# LOGIC_MCU.net
KiCad netlist of a schematic drawn in Altium Designer
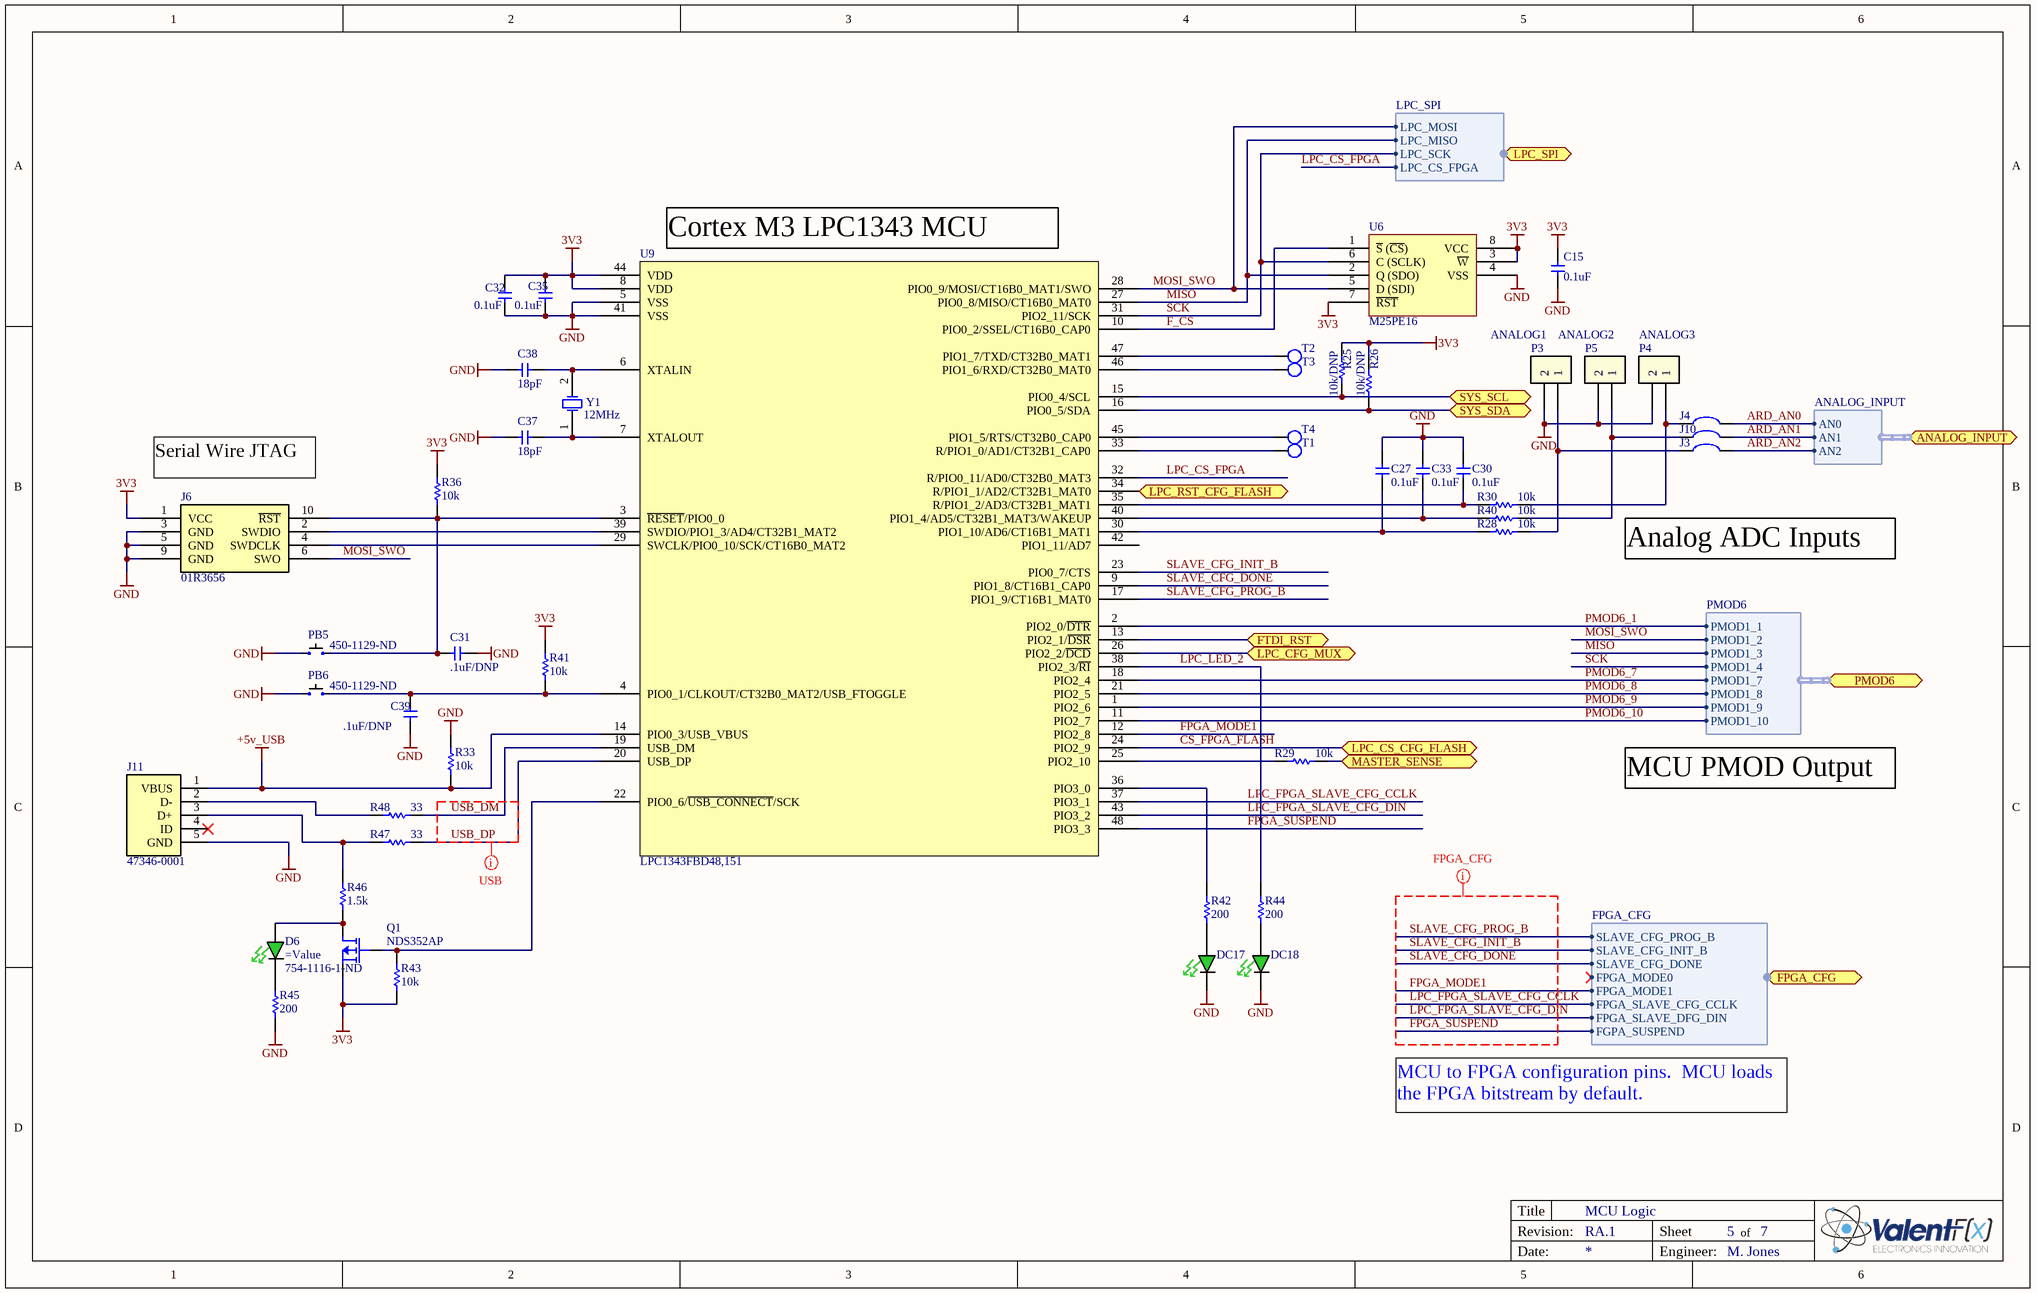
[diagram p0: LOGIC_MCU.SchDoc]

(export (version "E")
  (design (tool "Eeschema 10.0.6"))
  (components
    (comp (ref "C15")
      (value "0.1uF")
      (footprint "C0603")
      (description "CAP CER .1UF 50V 10% X7R 0603")
      (fields
        (field (name "MANUFACTURER") "Murata Electronics North America")
        (field (name "MANUFACTURER PART NUMBER") "GRM188R71H104KA93D")
      )
      (libsource (lib "Capacitors") (part "GRM188R71H104KA93D"))
    )
    (comp (ref "C27")
      (value "0.1uF")
      (footprint "C0603")
      (description "CAP CER .1UF 50V 10% X7R 0603")
      (fields
        (field (name "MANUFACTURER") "Murata Electronics North America")
        (field (name "MANUFACTURER PART NUMBER") "GRM188R71H104KA93D")
      )
      (libsource (lib "Capacitors") (part "GRM188R71H104KA93D"))
    )
    (comp (ref "C30")
      (value "0.1uF")
      (footprint "C0603")
      (description "CAP CER .1UF 50V 10% X7R 0603")
      (fields
        (field (name "MANUFACTURER") "Murata Electronics North America")
        (field (name "MANUFACTURER PART NUMBER") "GRM188R71H104KA93D")
      )
      (libsource (lib "Capacitors") (part "GRM188R71H104KA93D"))
    )
    (comp (ref "C31")
      (value ".1uF/DNP")
      (footprint "C0603")
      (description "CAP CER .1UF 50V 10% X7R 0603")
      (fields
        (field (name "MANUFACTURER") "Murata Electronics North America")
        (field (name "MANUFACTURER PART NUMBER") "GRM188R71H104KA93D")
      )
      (libsource (lib "Capacitors") (part "GRM188R71H104KA93D"))
    )
    (comp (ref "C32")
      (value "0.1uF")
      (footprint "C0603")
      (description "CAP CER .1UF 50V 10% X7R 0603")
      (fields
        (field (name "MANUFACTURER") "Murata Electronics North America")
        (field (name "MANUFACTURER PART NUMBER") "GRM188R71H104KA93D")
      )
      (libsource (lib "Capacitors") (part "GRM188R71H104KA93D"))
    )
    (comp (ref "C33")
      (value "0.1uF")
      (footprint "C0603")
      (description "CAP CER .1UF 50V 10% X7R 0603")
      (fields
        (field (name "MANUFACTURER") "Murata Electronics North America")
        (field (name "MANUFACTURER PART NUMBER") "GRM188R71H104KA93D")
      )
      (libsource (lib "Capacitors") (part "GRM188R71H104KA93D"))
    )
    (comp (ref "C35")
      (value "0.1uF")
      (footprint "C0603")
      (description "CAP CER .1UF 50V 10% X7R 0603")
      (fields
        (field (name "MANUFACTURER") "Murata Electronics North America")
        (field (name "MANUFACTURER PART NUMBER") "GRM188R71H104KA93D")
      )
      (libsource (lib "Capacitors") (part "GRM188R71H104KA93D"))
    )
    (comp (ref "C37")
      (value "18pF")
      (footprint "C0603")
      (description "CAP CER 18PF 50V 5% C0G 0603")
      (fields
        (field (name "MANUFACTURER") "Murata Electronics North America")
        (field (name "MANUFACTURER PART NUMBER") "GRM1885C1H180JA01D")
        (field (name "SOURCE") "Digikey")
      )
      (libsource (lib "Capacitors") (part "GRM1885C1H180JA01D"))
    )
    (comp (ref "C38")
      (value "18pF")
      (footprint "C0603")
      (description "CAP CER 18PF 50V 5% C0G 0603")
      (fields
        (field (name "MANUFACTURER") "Murata Electronics North America")
        (field (name "MANUFACTURER PART NUMBER") "GRM1885C1H180JA01D")
        (field (name "SOURCE") "Digikey")
      )
      (libsource (lib "Capacitors") (part "GRM1885C1H180JA01D"))
    )
    (comp (ref "C39")
      (value ".1uF/DNP")
      (footprint "C0603")
      (description "CAP CER .1UF 50V 10% X7R 0603")
      (fields
        (field (name "MANUFACTURER") "Murata Electronics North America")
        (field (name "MANUFACTURER PART NUMBER") "GRM188R71H104KA93D")
      )
      (libsource (lib "Capacitors") (part "GRM188R71H104KA93D"))
    )
    (comp (ref "D6")
      (value "~")
      (footprint "LED_0603 - GREEN")
      (description "LED 1.6X0.8MM 570NM GRN CLR SMD")
      (fields
        (field (name "SUPPLIER PART NUMBER 1") "754-1116-1-ND")
        (field (name "MANUFACTURER") "Kingbright Corp")
        (field (name "MANUFACTURER PART NUMBER") "APT1608CGCK")
      )
      (libsource (lib "mDiode") (part "APT1608CGCK"))
    )
    (comp (ref "DC17")
      (value "~")
      (footprint "LED_0603 - GREEN")
      (description "LED 1.6X0.8MM 570NM GRN CLR SMD")
      (fields
        (field (name "MANUFACTURER") "Kingbright Corp")
        (field (name "MANUFACTURER PART NUMBER") "APT1608CGCK")
      )
      (libsource (lib "mDiode") (part "APT1608CGCK"))
    )
    (comp (ref "DC18")
      (value "~")
      (footprint "LED_0603 - GREEN")
      (description "LED 1.6X0.8MM 570NM GRN CLR SMD")
      (fields
        (field (name "MANUFACTURER") "Kingbright Corp")
        (field (name "MANUFACTURER PART NUMBER") "APT1608CGCK")
      )
      (libsource (lib "mDiode") (part "APT1608CGCK"))
    )
    (comp (ref "J3")
      (value "Solder Jumper")
      (footprint "SOLDER_JUMPER SMALL 2")
      (description "Solder/Configuration Jumper")
      (fields (field (name "MANUFACTURER") "n/a"))
      (libsource (lib "mConnector") (part "Solder Jumper"))
    )
    (comp (ref "J4")
      (value "Solder Jumper")
      (footprint "SOLDER_JUMPER SMALL 2")
      (description "Solder/Configuration Jumper")
      (fields (field (name "MANUFACTURER") "n/a"))
      (libsource (lib "mConnector") (part "Solder Jumper"))
    )
    (comp (ref "J6")
      (value "01R3656")
      (footprint "FTSH-105-04-F-DV")
      (description "Cortex SWD Connector")
      (fields
        (field (name "MANUFACTURER") "SAMTEC")
        (field (name "MANUFACTURER PART NUMBER") "FTSH-105-04-F-DV")
      )
      (libsource (lib "eConnector") (part "Cortex SWD  Connector"))
    )
    (comp (ref "J10")
      (value "Solder Jumper")
      (footprint "SOLDER_JUMPER SMALL 2")
      (description "Solder/Configuration Jumper")
      (fields (field (name "MANUFACTURER") "n/a"))
      (libsource (lib "mConnector") (part "Solder Jumper"))
    )
    (comp (ref "J11")
      (value "47346-0001")
      (footprint "USB - 47346-0001")
      (description "Micro B CONN RCPT 5POS MICRO B USB R/A")
      (fields
        (field (name "MANUFACTURER") "Molex Inc")
        (field (name "MANUFACTURER PART NUMBER") "0473460001")
      )
      (libsource (lib "mConnector") (part "USB - 0473460001"))
    )
    (comp (ref "P3")
      (value "ANALOG1")
      (footprint "HEADER_2_30_100 THRU SIP")
      (description "Header 2 pin")
      (libsource (lib "mConnector") (part "Header2"))
    )
    (comp (ref "P4")
      (value "ANALOG3")
      (footprint "HEADER_2_30_100 THRU SIP")
      (description "Header 2 pin")
      (libsource (lib "mConnector") (part "Header2"))
    )
    (comp (ref "P5")
      (value "ANALOG2")
      (footprint "HEADER_2_30_100 THRU SIP")
      (description "Header 2 pin")
      (libsource (lib "mConnector") (part "Header2"))
    )
    (comp (ref "PB5")
      (value "~")
      (footprint "mElectroMechanical:FSM4JSMA")
      (description "SWITCH TACTILE SPST-NO 0.05A 12V")
      (fields
        (field (name "SUPPLIER PART NUMBER 1") "450-1129-ND")
        (field (name "MANUFACTURER") "TE Connectivity")
        (field (name "MANUFACTURER PART NUMBER") "FSM4JSMA")
      )
      (libsource (lib "mElectroMechanical") (part "FSM4JSMATR"))
    )
    (comp (ref "PB6")
      (value "~")
      (footprint "mElectroMechanical:FSM4JSMA")
      (description "SWITCH TACTILE SPST-NO 0.05A 12V")
      (fields
        (field (name "SUPPLIER PART NUMBER 1") "450-1129-ND")
        (field (name "MANUFACTURER") "TE Connectivity")
        (field (name "MANUFACTURER PART NUMBER") "FSM4JSMA")
      )
      (libsource (lib "mElectroMechanical") (part "FSM4JSMATR"))
    )
    (comp (ref "Q1")
      (value "NDS352AP")
      (footprint "SOT-23")
      (description "MOSFET P-CH 30V 900MA SSOT3")
      (fields (field (name "MANUFACTURER") "Fairchild Semiconductor"))
      (libsource (lib "Transistors") (part "NDS352AP"))
    )
    (comp (ref "R25")
      (value "10k/DNP")
      (footprint "R0603")
      (description "RES 10.0K OHM 1/10W 1% 0603 SMD")
      (fields
        (field (name "MANUFACTURER") "Panasonic - ECG")
        (field (name "TOLERANCE") "±1%")
        (field (name "SOURCE") "Digikey")
      )
      (libsource (lib "Resistors") (part "ERJ-3EKF1002V"))
    )
    (comp (ref "R26")
      (value "10k/DNP")
      (footprint "R0603")
      (description "RES 10.0K OHM 1/10W 1% 0603 SMD")
      (fields
        (field (name "MANUFACTURER") "Panasonic - ECG")
        (field (name "TOLERANCE") "±1%")
        (field (name "SOURCE") "Digikey")
      )
      (libsource (lib "Resistors") (part "ERJ-3EKF1002V"))
    )
    (comp (ref "R28")
      (value "10k")
      (footprint "R0603")
      (description "RES 10.0K OHM 1/10W 1% 0603 SMD")
      (fields
        (field (name "MANUFACTURER") "Panasonic - ECG")
        (field (name "TOLERANCE") "±1%")
        (field (name "SOURCE") "Digikey")
      )
      (libsource (lib "Resistors") (part "ERJ-3EKF1002V"))
    )
    (comp (ref "R29")
      (value "10k")
      (footprint "R0603")
      (description "RES 10.0K OHM 1/10W 1% 0603 SMD")
      (fields
        (field (name "MANUFACTURER") "Panasonic - ECG")
        (field (name "TOLERANCE") "±1%")
        (field (name "SOURCE") "Digikey")
      )
      (libsource (lib "Resistors") (part "ERJ-3EKF1002V"))
    )
    (comp (ref "R30")
      (value "10k")
      (footprint "R0603")
      (description "RES 10.0K OHM 1/10W 1% 0603 SMD")
      (fields
        (field (name "MANUFACTURER") "Panasonic - ECG")
        (field (name "TOLERANCE") "±1%")
        (field (name "SOURCE") "Digikey")
      )
      (libsource (lib "Resistors") (part "ERJ-3EKF1002V"))
    )
    (comp (ref "R33")
      (value "10k")
      (footprint "R0603")
      (description "RES 10.0K OHM 1/10W 1% 0603 SMD")
      (fields
        (field (name "MANUFACTURER") "Panasonic - ECG")
        (field (name "TOLERANCE") "±1%")
        (field (name "SOURCE") "Digikey")
      )
      (libsource (lib "Resistors") (part "ERJ-3EKF1002V"))
    )
    (comp (ref "R36")
      (value "10k")
      (footprint "R0603")
      (description "RES 10.0K OHM 1/10W 1% 0603 SMD")
      (fields
        (field (name "MANUFACTURER") "Panasonic - ECG")
        (field (name "TOLERANCE") "±1%")
        (field (name "SOURCE") "Digikey")
      )
      (libsource (lib "Resistors") (part "ERJ-3EKF1002V"))
    )
    (comp (ref "R40")
      (value "10k")
      (footprint "R0603")
      (description "RES 10.0K OHM 1/10W 1% 0603 SMD")
      (fields
        (field (name "MANUFACTURER") "Panasonic - ECG")
        (field (name "TOLERANCE") "±1%")
        (field (name "SOURCE") "Digikey")
      )
      (libsource (lib "Resistors") (part "ERJ-3EKF1002V"))
    )
    (comp (ref "R41")
      (value "10k")
      (footprint "R0603")
      (description "RES 10.0K OHM 1/10W 1% 0603 SMD")
      (fields
        (field (name "MANUFACTURER") "Panasonic - ECG")
        (field (name "TOLERANCE") "±1%")
        (field (name "SOURCE") "Digikey")
      )
      (libsource (lib "Resistors") (part "ERJ-3EKF1002V"))
    )
    (comp (ref "R42")
      (value "200")
      (footprint "R0603")
      (description "RES 200 OHM 1/10W 1% 0603 SMD")
      (fields
        (field (name "MANUFACTURER") "Panasonic - ECG")
        (field (name "MANUFACTURER PART NUMBER") "ERJ-3EKF2000V")
      )
      (libsource (lib "eResistors") (part "ERJ-3EKF2000V"))
    )
    (comp (ref "R43")
      (value "10k")
      (footprint "R0603")
      (description "RES 10.0K OHM 1/10W 1% 0603 SMD")
      (fields
        (field (name "MANUFACTURER") "Panasonic - ECG")
        (field (name "TOLERANCE") "±1%")
        (field (name "SOURCE") "Digikey")
      )
      (libsource (lib "Resistors") (part "ERJ-3EKF1002V"))
    )
    (comp (ref "R44")
      (value "200")
      (footprint "R0603")
      (description "RES 200 OHM 1/10W 1% 0603 SMD")
      (fields
        (field (name "MANUFACTURER") "Panasonic - ECG")
        (field (name "MANUFACTURER PART NUMBER") "ERJ-3EKF2000V")
      )
      (libsource (lib "eResistors") (part "ERJ-3EKF2000V"))
    )
    (comp (ref "R45")
      (value "200")
      (footprint "R0603")
      (description "RES 200 OHM 1/10W 1% 0603 SMD")
      (fields
        (field (name "MANUFACTURER") "Panasonic - ECG")
        (field (name "MANUFACTURER PART NUMBER") "ERJ-3EKF2000V")
      )
      (libsource (lib "eResistors") (part "ERJ-3EKF2000V"))
    )
    (comp (ref "R46")
      (value "1.5k")
      (footprint "R0603")
      (description "RES 1.50K OHM 1/10W 1% 0603 SMD")
      (fields
        (field (name "MANUFACTURER") "Panasonic - ECG")
        (field (name "MANUFACTURER PART NUMBER") "ERJ-3EKF1501V")
      )
      (libsource (lib "Resistors") (part "ERJ-3EKF1501V"))
    )
    (comp (ref "R47")
      (value "33")
      (footprint "R0603")
      (description "RES 33.0 OHM 1/10W 1% 0603 SMD")
      (fields
        (field (name "MANUFACTURER") "Panasonic - ECG")
        (field (name "MANUFACTURER PART NUMBER") "ERJ-3EKF33R0V")
      )
      (libsource (lib "Resistors") (part "ERJ-3EKF33R0V"))
    )
    (comp (ref "R48")
      (value "33")
      (footprint "R0603")
      (description "RES 33.0 OHM 1/10W 1% 0603 SMD")
      (fields
        (field (name "MANUFACTURER") "Panasonic - ECG")
        (field (name "MANUFACTURER PART NUMBER") "ERJ-3EKF33R0V")
      )
      (libsource (lib "Resistors") (part "ERJ-3EKF33R0V"))
    )
    (comp (ref "T1")
      (value "Test Point")
      (footprint "tp 18-28")
      (description "Test Point Smaller Symbol")
      (libsource (lib "mConnector") (part "Test Point 2"))
    )
    (comp (ref "T2")
      (value "Test Point")
      (footprint "tp 18-28")
      (description "Test Point Smaller Symbol")
      (libsource (lib "mConnector") (part "Test Point 2"))
    )
    (comp (ref "T3")
      (value "Test Point")
      (footprint "tp 18-28")
      (description "Test Point Smaller Symbol")
      (libsource (lib "mConnector") (part "Test Point 2"))
    )
    (comp (ref "T4")
      (value "Test Point")
      (footprint "tp 18-28")
      (description "Test Point Smaller Symbol")
      (libsource (lib "mConnector") (part "Test Point 2"))
    )
    (comp (ref "U6")
      (value "M25PE16")
      (footprint "SOIC127P830X200-8L")
      (description "IC FLASH 16MBIT 75MHZ 8SOIC")
      (fields
        (field (name "MANUFACTURER") "Numonyx/ST Micro")
        (field (name "MANUFACTURER PART NUMBER") "M25PE16-VMW6TG")
      )
      (libsource (lib "ICs") (part "M25PE16-VMW6TG"))
    )
    (comp (ref "U9")
      (value "LPC1343FBD48,151")
      (footprint "TSQFP50P900X900X145-48L")
      (description "IC MCU 32BIT 32KB FLASH 48LQFP")
      (fields (field (name "MANUFACTURER") "NXP Semiconductors"))
      (libsource (lib "eIC") (part "LPC1343FBD48,151"))
    )
    (comp (ref "Y1")
      (value "12MHz")
      (footprint "ABM3")
      (description "CRYSTAL 12.000MHZ 18PF SMD")
      (fields
        (field (name "MANUFACTURER") "Abracon Corporation")
        (field (name "MANUFACTURER PART NUMBER") "ABM3-12.000MHZ-B2-T")
      )
      (libsource (lib "Crystals") (part "ABM3-12.000MHZ-B2-T"))
    )
  )
  (nets
    (net (code "5") (name "+5v_USB") (class "Default")
      (node (ref "J11") (pin "1") (pinfunction "VBUS_1") (pintype "passive"))
      (node (ref "R33") (pin "2") (pinfunction "2_2") (pintype "passive"))
      (node (ref "U9") (pin "14") (pinfunction "PIO0_3/USB_VBUS_14") (pintype "passive"))
    )
    (net (code "6") (name "/ARD_AN0") (class "Default")
      (node (ref "J4") (pin "2") (pinfunction "2_2") (pintype "passive"))
    )
    (net (code "7") (name "/ARD_AN1") (class "Default")
      (node (ref "J10") (pin "2") (pinfunction "2_2") (pintype "passive"))
    )
    (net (code "8") (name "/ARD_AN2") (class "Default")
      (node (ref "J3") (pin "2") (pinfunction "2_2") (pintype "passive"))
    )
    (net (code "9") (name "/CS_FPGA_FLASH") (class "Default")
      (node (ref "U9") (pin "24") (pinfunction "PIO2_9_24") (pintype "passive"))
    )
    (net (code "10") (name "/FPGA_MODE1") (class "Default")
      (node (ref "U9") (pin "12") (pinfunction "PIO2_8_12") (pintype "passive"))
    )
    (net (code "11") (name "/FPGA_SUSPEND") (class "Default")
      (node (ref "U9") (pin "48") (pinfunction "PIO3_3_48") (pintype "passive"))
    )
    (net (code "12") (name "/FTDI_RST") (class "Default")
      (node (ref "U9") (pin "13") (pinfunction "PIO2_1/~{DSR}_13") (pintype "passive"))
    )
    (net (code "13") (name "/F_CS") (class "Default")
      (node (ref "U6") (pin "1") (pinfunction "~{S}_(~{CS})_1") (pintype "passive"))
      (node (ref "U9") (pin "10") (pinfunction "PIO0_2/SSEL/CT16B0_CAP0_10") (pintype "passive"))
    )
    (net (code "14") (name "/LPC_CFG_MUX") (class "Default")
      (node (ref "U9") (pin "26") (pinfunction "PIO2_2/~{DCD}_26") (pintype "passive"))
    )
    (net (code "15") (name "/LPC_CS_FPGA") (class "Default")
      (node (ref "U9") (pin "32") (pinfunction "R/PIO0_11/AD0/CT32B0_MAT3_32") (pintype "passive"))
    )
    (net (code "16") (name "/LPC_FPGA_SLAVE_CFG_CCLK") (class "Default")
      (node (ref "U9") (pin "37") (pinfunction "PIO3_1_37") (pintype "passive"))
    )
    (net (code "17") (name "/LPC_FPGA_SLAVE_CFG_DIN") (class "Default")
      (node (ref "U9") (pin "43") (pinfunction "PIO3_2_43") (pintype "passive"))
    )
    (net (code "18") (name "/LPC_LED_2") (class "Default")
      (node (ref "R44") (pin "1") (pinfunction "1_1") (pintype "passive"))
      (node (ref "U9") (pin "38") (pinfunction "PIO2_3/~{RI}_38") (pintype "passive"))
    )
    (net (code "19") (name "/LPC_RST_CFG_FLASH") (class "Default")
      (node (ref "U9") (pin "34") (pinfunction "R/PIO1_1/AD2/CT32B1_MAT0_34") (pintype "passive"))
    )
    (net (code "20") (name "/MASTER_SENSE") (class "Default")
      (node (ref "R29") (pin "2") (pinfunction "2_2") (pintype "passive"))
    )
    (net (code "21") (name "/MISO") (class "Default")
      (node (ref "U6") (pin "2") (pinfunction "Q_(SDO)_2") (pintype "passive"))
      (node (ref "U9") (pin "27") (pinfunction "PIO0_8/MISO/CT16B0_MAT0_27") (pintype "passive"))
    )
    (net (code "22") (name "/MOSI_SWO") (class "Default")
      (node (ref "J6") (pin "6") (pinfunction "SWO_6") (pintype "passive"))
      (node (ref "U6") (pin "5") (pinfunction "D_(SDI)_5") (pintype "passive"))
      (node (ref "U9") (pin "28") (pinfunction "PIO0_9/MOSI/CT16B0_MAT1/SWO_28") (pintype "passive"))
    )
    (net (code "23") (name "/PMOD6_1") (class "Default")
      (node (ref "U9") (pin "2") (pinfunction "PIO2_0/~{DTR}_2") (pintype "passive"))
    )
    (net (code "24") (name "/PMOD6_7") (class "Default")
      (node (ref "U9") (pin "18") (pinfunction "PIO2_4_18") (pintype "passive"))
    )
    (net (code "25") (name "/PMOD6_8") (class "Default")
      (node (ref "U9") (pin "21") (pinfunction "PIO2_5_21") (pintype "passive"))
    )
    (net (code "26") (name "/PMOD6_9") (class "Default")
      (node (ref "U9") (pin "1") (pinfunction "PIO2_6_1") (pintype "passive"))
    )
    (net (code "27") (name "/PMOD6_10") (class "Default")
      (node (ref "U9") (pin "11") (pinfunction "PIO2_7_11") (pintype "passive"))
    )
    (net (code "28") (name "/SCK") (class "Default")
      (node (ref "U6") (pin "6") (pinfunction "C_(SCLK)_6") (pintype "passive"))
      (node (ref "U9") (pin "31") (pinfunction "PIO2_11/SCK_31") (pintype "passive"))
    )
    (net (code "29") (name "/SLAVE_CFG_DONE") (class "Default")
      (node (ref "U9") (pin "9") (pinfunction "PIO1_8/CT16B1_CAP0_9") (pintype "passive"))
    )
    (net (code "30") (name "/SLAVE_CFG_INIT_B") (class "Default")
      (node (ref "U9") (pin "23") (pinfunction "PIO0_7/CTS_23") (pintype "passive"))
    )
    (net (code "31") (name "/SLAVE_CFG_PROG_B") (class "Default")
      (node (ref "U9") (pin "17") (pinfunction "PIO1_9/CT16B1_MAT0_17") (pintype "passive"))
    )
    (net (code "32") (name "/SYS_SCL") (class "Default")
      (node (ref "R25") (pin "1") (pinfunction "1_1") (pintype "passive"))
      (node (ref "U9") (pin "15") (pinfunction "PIO0_4/SCL_15") (pintype "passive"))
    )
    (net (code "33") (name "/SYS_SDA") (class "Default")
      (node (ref "R26") (pin "1") (pinfunction "1_1") (pintype "passive"))
      (node (ref "U9") (pin "16") (pinfunction "PIO0_5/SDA_16") (pintype "passive"))
    )
    (net (code "34") (name "/USB_DM") (class "Default")
      (node (ref "R48") (pin "2") (pinfunction "2_2") (pintype "passive"))
      (node (ref "U9") (pin "19") (pinfunction "USB_DM_19") (pintype "passive"))
    )
    (net (code "35") (name "/USB_DP") (class "Default")
      (node (ref "R47") (pin "2") (pinfunction "2_2") (pintype "passive"))
      (node (ref "U9") (pin "20") (pinfunction "USB_DP_20") (pintype "passive"))
    )
    (net (code "40") (name "3V3") (class "Default")
      (node (ref "C15") (pin "2") (pinfunction "2_2") (pintype "passive"))
      (node (ref "C32") (pin "2") (pinfunction "2_2") (pintype "passive"))
      (node (ref "C35") (pin "2") (pinfunction "2_2") (pintype "passive"))
      (node (ref "J6") (pin "1") (pinfunction "VCC_1") (pintype "passive"))
      (node (ref "Q1") (pin "2") (pinfunction "S_2") (pintype "passive"))
      (node (ref "R25") (pin "2") (pinfunction "2_2") (pintype "passive"))
      (node (ref "R26") (pin "2") (pinfunction "2_2") (pintype "passive"))
      (node (ref "R36") (pin "1") (pinfunction "1_1") (pintype "passive"))
      (node (ref "R41") (pin "1") (pinfunction "1_1") (pintype "passive"))
      (node (ref "R43") (pin "2") (pinfunction "2_2") (pintype "passive"))
      (node (ref "U6") (pin "3") (pinfunction "~{W}_3") (pintype "passive"))
      (node (ref "U6") (pin "7") (pinfunction "~{RST}_7") (pintype "passive"))
      (node (ref "U6") (pin "8") (pinfunction "VCC_8") (pintype "passive"))
      (node (ref "U9") (pin "44") (pinfunction "VDD_44") (pintype "passive"))
      (node (ref "U9") (pin "8") (pinfunction "VDD_8") (pintype "passive"))
    )
    (net (code "41") (name "GND") (class "Default")
      (node (ref "C15") (pin "1") (pinfunction "1_1") (pintype "passive"))
      (node (ref "C27") (pin "2") (pinfunction "2_2") (pintype "passive"))
      (node (ref "C30") (pin "2") (pinfunction "2_2") (pintype "passive"))
      (node (ref "C31") (pin "1") (pinfunction "1_1") (pintype "passive"))
      (node (ref "C32") (pin "1") (pinfunction "1_1") (pintype "passive"))
      (node (ref "C33") (pin "2") (pinfunction "2_2") (pintype "passive"))
      (node (ref "C35") (pin "1") (pinfunction "1_1") (pintype "passive"))
      (node (ref "C37") (pin "1") (pinfunction "1_1") (pintype "passive"))
      (node (ref "C38") (pin "1") (pinfunction "1_1") (pintype "passive"))
      (node (ref "C39") (pin "1") (pinfunction "1_1") (pintype "passive"))
      (node (ref "DC17") (pin "C") (pinfunction "C_C") (pintype "passive"))
      (node (ref "DC18") (pin "C") (pinfunction "C_C") (pintype "passive"))
      (node (ref "J11") (pin "5") (pinfunction "GND_5") (pintype "passive"))
      (node (ref "J6") (pin "3") (pinfunction "GND_3") (pintype "passive"))
      (node (ref "J6") (pin "5") (pinfunction "GND_5") (pintype "passive"))
      (node (ref "J6") (pin "9") (pinfunction "GND_9") (pintype "passive"))
      (node (ref "P3") (pin "2") (pinfunction "2_2") (pintype "passive"))
      (node (ref "P4") (pin "2") (pinfunction "2_2") (pintype "passive"))
      (node (ref "P5") (pin "2") (pinfunction "2_2") (pintype "passive"))
      (node (ref "PB5") (pin "A") (pinfunction "A_A") (pintype "passive"))
      (node (ref "PB6") (pin "A") (pinfunction "A_A") (pintype "passive"))
      (node (ref "R33") (pin "1") (pinfunction "1_1") (pintype "passive"))
      (node (ref "R45") (pin "1") (pinfunction "1_1") (pintype "passive"))
      (node (ref "U6") (pin "4") (pinfunction "VSS_4") (pintype "passive"))
      (node (ref "U9") (pin "41") (pinfunction "VSS_41") (pintype "passive"))
      (node (ref "U9") (pin "5") (pinfunction "VSS_5") (pintype "passive"))
    )
    (net (code "42") (name "Net-(D6-PadC)") (class "Default")
      (node (ref "D6") (pin "C") (pinfunction "C_C") (pintype "passive"))
      (node (ref "R45") (pin "2") (pinfunction "2_2") (pintype "passive"))
    )
    (net (code "43") (name "Net-(DC17-PadA)") (class "Default")
      (node (ref "DC17") (pin "A") (pinfunction "A_A") (pintype "passive"))
      (node (ref "R42") (pin "2") (pinfunction "2_2") (pintype "passive"))
    )
    (net (code "44") (name "Net-(DC18-PadA)") (class "Default")
      (node (ref "DC18") (pin "A") (pinfunction "A_A") (pintype "passive"))
      (node (ref "R44") (pin "2") (pinfunction "2_2") (pintype "passive"))
    )
    (net (code "45") (name "Net-(J3-Pad1)") (class "Default")
      (node (ref "J3") (pin "1") (pinfunction "1_1") (pintype "passive"))
      (node (ref "P3") (pin "1") (pinfunction "1_1") (pintype "passive"))
      (node (ref "R28") (pin "2") (pinfunction "2_2") (pintype "passive"))
    )
    (net (code "46") (name "Net-(J4-Pad1)") (class "Default")
      (node (ref "J4") (pin "1") (pinfunction "1_1") (pintype "passive"))
      (node (ref "P4") (pin "1") (pinfunction "1_1") (pintype "passive"))
      (node (ref "R30") (pin "2") (pinfunction "2_2") (pintype "passive"))
    )
    (net (code "47") (name "Net-(J6-SWDCLK)") (class "Default")
      (node (ref "J6") (pin "4") (pinfunction "SWDCLK_4") (pintype "passive"))
      (node (ref "U9") (pin "29") (pinfunction "SWCLK/PIO0_10/SCK/CT16B0_MAT2_29") (pintype "passive"))
    )
    (net (code "48") (name "Net-(J6-SWDIO)") (class "Default")
      (node (ref "J6") (pin "2") (pinfunction "SWDIO_2") (pintype "passive"))
      (node (ref "U9") (pin "39") (pinfunction "SWDIO/PIO1_3/AD4/CT32B1_MAT2_39") (pintype "passive"))
    )
    (net (code "49") (name "Net-(J6-~{RST})") (class "Default")
      (node (ref "C31") (pin "2") (pinfunction "2_2") (pintype "passive"))
      (node (ref "J6") (pin "10") (pinfunction "~{RST}_10") (pintype "passive"))
      (node (ref "PB5") (pin "B") (pinfunction "B_B") (pintype "passive"))
      (node (ref "R36") (pin "2") (pinfunction "2_2") (pintype "passive"))
      (node (ref "U9") (pin "3") (pinfunction "~{RESET}/PIO0_0_3") (pintype "passive"))
    )
    (net (code "50") (name "Net-(J10-Pad1)") (class "Default")
      (node (ref "J10") (pin "1") (pinfunction "1_1") (pintype "passive"))
      (node (ref "P5") (pin "1") (pinfunction "1_1") (pintype "passive"))
      (node (ref "R40") (pin "2") (pinfunction "2_2") (pintype "passive"))
    )
    (net (code "51") (name "Net-(J11-D+)") (class "Default")
      (node (ref "J11") (pin "3") (pinfunction "D+_3") (pintype "passive"))
      (node (ref "R46") (pin "2") (pinfunction "2_2") (pintype "passive"))
      (node (ref "R47") (pin "1") (pinfunction "1_1") (pintype "passive"))
    )
    (net (code "52") (name "Net-(J11-D-)") (class "Default")
      (node (ref "J11") (pin "2") (pinfunction "D-_2") (pintype "passive"))
      (node (ref "R48") (pin "1") (pinfunction "1_1") (pintype "passive"))
    )
    (net (code "53") (name "Net-(Q1-D)") (class "Default")
      (node (ref "D6") (pin "A") (pinfunction "A_A") (pintype "passive"))
      (node (ref "Q1") (pin "3") (pinfunction "D_3") (pintype "passive"))
      (node (ref "R46") (pin "1") (pinfunction "1_1") (pintype "passive"))
    )
    (net (code "54") (name "Net-(Q1-G)") (class "Default")
      (node (ref "Q1") (pin "1") (pinfunction "G_1") (pintype "passive"))
      (node (ref "R43") (pin "1") (pinfunction "1_1") (pintype "passive"))
      (node (ref "U9") (pin "22") (pinfunction "PIO0_6/~{USB_CONNECT}/SCK_22") (pintype "passive"))
    )
    (net (code "55") (name "Net-(U9-PIO0_1{slash}CLKOUT{slash}CT32B0_MAT2{slash}USB_FTOGGLE)") (class "Default")
      (node (ref "C39") (pin "2") (pinfunction "2_2") (pintype "passive"))
      (node (ref "PB6") (pin "B") (pinfunction "B_B") (pintype "passive"))
      (node (ref "R41") (pin "2") (pinfunction "2_2") (pintype "passive"))
      (node (ref "U9") (pin "4") (pinfunction "PIO0_1/CLKOUT/CT32B0_MAT2/USB_FTOGGLE_4") (pintype "passive"))
    )
    (net (code "56") (name "Net-(U9-PIO1_4{slash}AD5{slash}CT32B1_MAT3{slash}WAKEUP)") (class "Default")
      (node (ref "C33") (pin "1") (pinfunction "1_1") (pintype "passive"))
      (node (ref "R40") (pin "1") (pinfunction "1_1") (pintype "passive"))
      (node (ref "U9") (pin "40") (pinfunction "PIO1_4/AD5/CT32B1_MAT3/WAKEUP_40") (pintype "passive"))
    )
    (net (code "57") (name "Net-(U9-PIO1_5{slash}RTS{slash}CT32B0_CAP0)") (class "Default")
      (node (ref "T4") (pin "1") (pinfunction "1_1") (pintype "passive"))
      (node (ref "U9") (pin "45") (pinfunction "PIO1_5/RTS/CT32B0_CAP0_45") (pintype "passive"))
    )
    (net (code "58") (name "Net-(U9-PIO1_6{slash}RXD{slash}CT32B0_MAT0)") (class "Default")
      (node (ref "T3") (pin "1") (pinfunction "1_1") (pintype "passive"))
      (node (ref "U9") (pin "46") (pinfunction "PIO1_6/RXD/CT32B0_MAT0_46") (pintype "passive"))
    )
    (net (code "59") (name "Net-(U9-PIO1_7{slash}TXD{slash}CT32B0_MAT1)") (class "Default")
      (node (ref "T2") (pin "1") (pinfunction "1_1") (pintype "passive"))
      (node (ref "U9") (pin "47") (pinfunction "PIO1_7/TXD/CT32B0_MAT1_47") (pintype "passive"))
    )
    (net (code "60") (name "Net-(U9-PIO1_10{slash}AD6{slash}CT16B1_MAT1)") (class "Default")
      (node (ref "C27") (pin "1") (pinfunction "1_1") (pintype "passive"))
      (node (ref "R28") (pin "1") (pinfunction "1_1") (pintype "passive"))
      (node (ref "U9") (pin "30") (pinfunction "PIO1_10/AD6/CT16B1_MAT1_30") (pintype "passive"))
    )
    (net (code "61") (name "Net-(U9-PIO2_10)") (class "Default")
      (node (ref "R29") (pin "1") (pinfunction "1_1") (pintype "passive"))
      (node (ref "U9") (pin "25") (pinfunction "PIO2_10_25") (pintype "passive"))
    )
    (net (code "62") (name "Net-(U9-PIO3_0)") (class "Default")
      (node (ref "R42") (pin "1") (pinfunction "1_1") (pintype "passive"))
      (node (ref "U9") (pin "36") (pinfunction "PIO3_0_36") (pintype "passive"))
    )
    (net (code "63") (name "Net-(U9-R{slash}PIO1_0{slash}AD1{slash}CT32B1_CAP0)") (class "Default")
      (node (ref "T1") (pin "1") (pinfunction "1_1") (pintype "passive"))
      (node (ref "U9") (pin "33") (pinfunction "R/PIO1_0/AD1/CT32B1_CAP0_33") (pintype "passive"))
    )
    (net (code "64") (name "Net-(U9-R{slash}PIO1_2{slash}AD3{slash}CT32B1_MAT1)") (class "Default")
      (node (ref "C30") (pin "1") (pinfunction "1_1") (pintype "passive"))
      (node (ref "R30") (pin "1") (pinfunction "1_1") (pintype "passive"))
      (node (ref "U9") (pin "35") (pinfunction "R/PIO1_2/AD3/CT32B1_MAT1_35") (pintype "passive"))
    )
    (net (code "65") (name "Net-(U9-XTALIN)") (class "Default")
      (node (ref "C38") (pin "2") (pinfunction "2_2") (pintype "passive"))
      (node (ref "U9") (pin "6") (pinfunction "XTALIN_6") (pintype "passive"))
      (node (ref "Y1") (pin "2") (pinfunction "OSC2_2") (pintype "passive"))
    )
    (net (code "66") (name "Net-(U9-XTALOUT)") (class "Default")
      (node (ref "C37") (pin "2") (pinfunction "2_2") (pintype "passive"))
      (node (ref "U9") (pin "7") (pinfunction "XTALOUT_7") (pintype "passive"))
      (node (ref "Y1") (pin "1") (pinfunction "OSC1_1") (pintype "passive"))
    )
    (net (code "67") (name "unconnected-(J11-ID-Pad4)") (class "Default")
      (node (ref "J11") (pin "4") (pinfunction "ID_4") (pintype "passive+no_connect"))
    )
    (net (code "68") (name "unconnected-(U9-PIO1_11{slash}AD7-Pad42)") (class "Default")
      (node (ref "U9") (pin "42") (pinfunction "PIO1_11/AD7_42") (pintype "passive"))
    )
  )
)
